# hw2.net
KiCad netlist of a schematic drawn in EAGLE
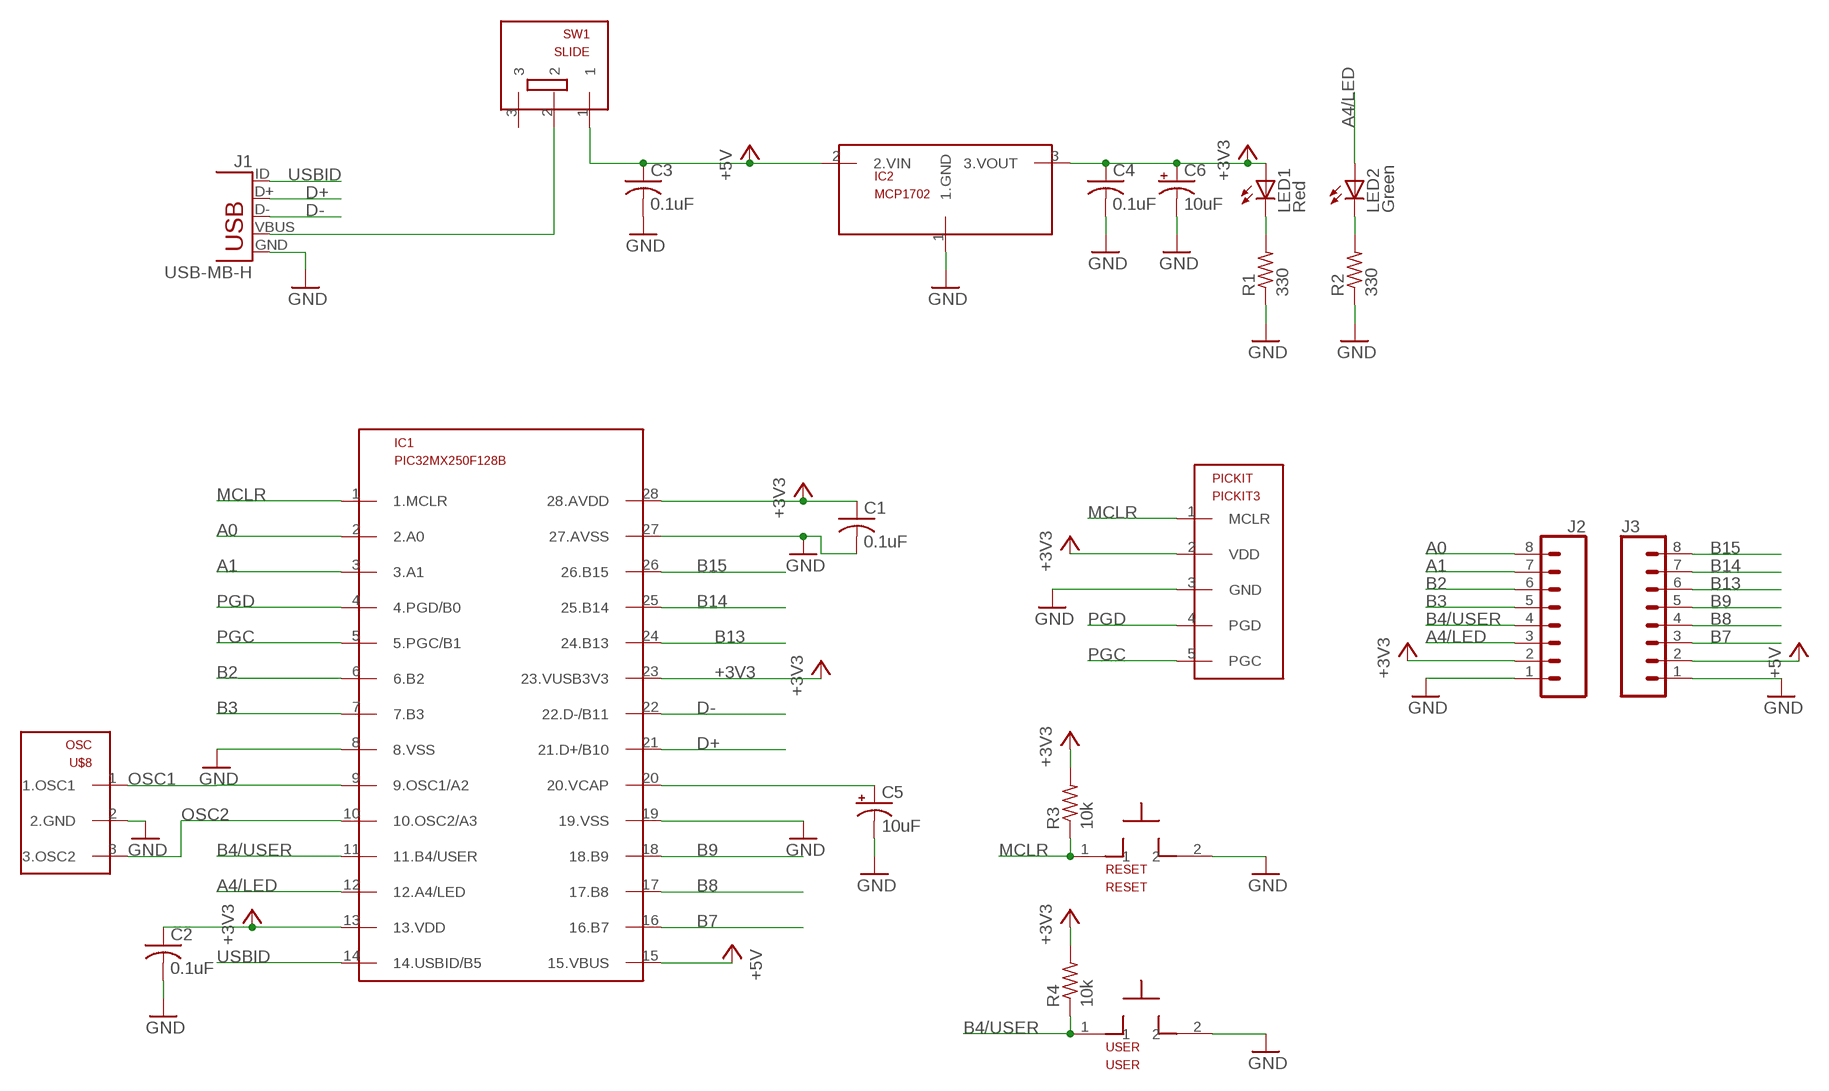
[diagram p0: schematic, sheet 1]

(export (version "E")
  (design (tool "Eeschema 10.0.6"))
  (components
    (comp (ref "C1")
      (value "0.1uF")
      (footprint "eagle-import:C025-025X050")
      (libsource (lib "eagle-import") (part "C-US025-025X050"))
    )
    (comp (ref "C2")
      (value "0.1uF")
      (footprint "eagle-import:C025-025X050")
      (libsource (lib "eagle-import") (part "C-US025-025X050"))
    )
    (comp (ref "C3")
      (value "0.1uF")
      (footprint "eagle-import:C025-025X050")
      (libsource (lib "eagle-import") (part "C-US025-025X050"))
    )
    (comp (ref "C4")
      (value "0.1uF")
      (footprint "eagle-import:C025-025X050")
      (libsource (lib "eagle-import") (part "C-US025-025X050"))
    )
    (comp (ref "C5")
      (value "10uF")
      (footprint "eagle-import:B45181B")
      (libsource (lib "eagle-import") (part "CPOL-USB45181B"))
    )
    (comp (ref "C6")
      (value "10uF")
      (footprint "eagle-import:B45181B")
      (libsource (lib "eagle-import") (part "CPOL-USB45181B"))
    )
    (comp (ref "IC1")
      (value "PIC32MX250F128B")
      (footprint "eagle-import:DIL28-3")
      (libsource (lib "eagle-import") (part "PIC32MX250F128B"))
    )
    (comp (ref "IC2")
      (value "MCP1702")
      (footprint "eagle-import:TO92")
      (libsource (lib "eagle-import") (part "MCP1702"))
    )
    (comp (ref "J1")
      (value "USB-MB-H")
      (footprint "eagle-import:USB-MB-H")
      (libsource (lib "eagle-import") (part "USB-MB-H"))
    )
    (comp (ref "J2")
      (value "CONN_08\"")
      (footprint "eagle-import:1X08")
      (libsource (lib "eagle-import") (part "CONN_08{dblquote}"))
    )
    (comp (ref "J3")
      (value "CONN_08\"")
      (footprint "eagle-import:1X08")
      (libsource (lib "eagle-import") (part "CONN_08{dblquote}"))
    )
    (comp (ref "LED1")
      (value "Red")
      (footprint "eagle-import:LED3MM")
      (libsource (lib "eagle-import") (part "LED3MM"))
    )
    (comp (ref "LED2")
      (value "Green")
      (footprint "eagle-import:LED3MM")
      (libsource (lib "eagle-import") (part "LED3MM"))
    )
    (comp (ref "PICKIT")
      (value "PICKIT3")
      (footprint "eagle-import:1X05")
      (libsource (lib "eagle-import") (part "PICKIT3"))
    )
    (comp (ref "R1")
      (value "330")
      (footprint "eagle-import:0207_10")
      (libsource (lib "eagle-import") (part "R-US_0207/10"))
    )
    (comp (ref "R2")
      (value "330")
      (footprint "eagle-import:0207_10")
      (libsource (lib "eagle-import") (part "R-US_0207/10"))
    )
    (comp (ref "R3")
      (value "10k")
      (footprint "eagle-import:0207_10")
      (libsource (lib "eagle-import") (part "R-US_0207/10"))
    )
    (comp (ref "R4")
      (value "10k")
      (footprint "eagle-import:0207_10")
      (libsource (lib "eagle-import") (part "R-US_0207/10"))
    )
    (comp (ref "RESET")
      (value "RESET")
      (footprint "eagle-import:PB")
      (libsource (lib "eagle-import") (part "PB"))
    )
    (comp (ref "SW1")
      (value "SLIDE")
      (footprint "eagle-import:SLIDE")
      (libsource (lib "eagle-import") (part "SLIDE"))
    )
    (comp (ref "U$8")
      (value "OSC")
      (footprint "eagle-import:OSC")
      (libsource (lib "eagle-import") (part "OSC"))
    )
    (comp (ref "USER")
      (value "USER")
      (footprint "eagle-import:PB")
      (libsource (lib "eagle-import") (part "PB"))
    )
  )
  (nets
    (net (code "1") (name "+3V3") (class "Default")
      (node (ref "C1") (pin "1") (pinfunction "1_1") (pintype "passive"))
      (node (ref "C2") (pin "1") (pinfunction "1_1") (pintype "passive"))
      (node (ref "C4") (pin "1") (pinfunction "1_1") (pintype "passive"))
      (node (ref "C6") (pin "+") (pinfunction "+_+") (pintype "passive"))
      (node (ref "IC1") (pin "13") (pinfunction "13.VDD_13") (pintype "bidirectional"))
      (node (ref "IC1") (pin "23") (pinfunction "23.VUSB3V3_23") (pintype "bidirectional"))
      (node (ref "IC1") (pin "28") (pinfunction "28.AVDD_28") (pintype "bidirectional"))
      (node (ref "IC2") (pin "3") (pinfunction "3.VOUT_3") (pintype "bidirectional"))
      (node (ref "J2") (pin "2") (pinfunction "2_2") (pintype "passive"))
      (node (ref "LED1") (pin "A") (pinfunction "A_A") (pintype "passive"))
      (node (ref "PICKIT") (pin "2") (pinfunction "VDD_2") (pintype "bidirectional"))
      (node (ref "R3") (pin "2") (pinfunction "2_2") (pintype "passive"))
      (node (ref "R4") (pin "2") (pinfunction "2_2") (pintype "passive"))
    )
    (net (code "2") (name "+5V") (class "Default")
      (node (ref "C3") (pin "1") (pinfunction "1_1") (pintype "passive"))
      (node (ref "IC1") (pin "15") (pinfunction "15.VBUS_15") (pintype "bidirectional"))
      (node (ref "IC2") (pin "2") (pinfunction "2.VIN_2") (pintype "bidirectional"))
      (node (ref "J3") (pin "2") (pinfunction "2_2") (pintype "passive"))
      (node (ref "SW1") (pin "1") (pinfunction "1_1") (pintype "bidirectional"))
    )
    (net (code "3") (name "/A0") (class "Default")
      (node (ref "IC1") (pin "2") (pinfunction "2.A0_2") (pintype "bidirectional"))
      (node (ref "J2") (pin "8") (pinfunction "8_8") (pintype "passive"))
    )
    (net (code "4") (name "/A1") (class "Default")
      (node (ref "IC1") (pin "3") (pinfunction "3.A1_3") (pintype "bidirectional"))
      (node (ref "J2") (pin "7") (pinfunction "7_7") (pintype "passive"))
    )
    (net (code "5") (name "/A4{slash}LED") (class "Default")
      (node (ref "IC1") (pin "12") (pinfunction "12.A4/LED_12") (pintype "bidirectional"))
      (node (ref "J2") (pin "3") (pinfunction "3_3") (pintype "passive"))
      (node (ref "LED2") (pin "A") (pinfunction "A_A") (pintype "passive"))
    )
    (net (code "6") (name "/B2") (class "Default")
      (node (ref "IC1") (pin "6") (pinfunction "6.B2_6") (pintype "bidirectional"))
      (node (ref "J2") (pin "6") (pinfunction "6_6") (pintype "passive"))
    )
    (net (code "7") (name "/B3") (class "Default")
      (node (ref "IC1") (pin "7") (pinfunction "7.B3_7") (pintype "bidirectional"))
      (node (ref "J2") (pin "5") (pinfunction "5_5") (pintype "passive"))
    )
    (net (code "8") (name "/B4{slash}USER") (class "Default")
      (node (ref "IC1") (pin "11") (pinfunction "11.B4/USER_11") (pintype "bidirectional"))
      (node (ref "J2") (pin "4") (pinfunction "4_4") (pintype "passive"))
      (node (ref "R4") (pin "1") (pinfunction "1_1") (pintype "passive"))
      (node (ref "USER") (pin "1") (pinfunction "1_1") (pintype "bidirectional"))
    )
    (net (code "9") (name "/B7") (class "Default")
      (node (ref "IC1") (pin "16") (pinfunction "16.B7_16") (pintype "bidirectional"))
      (node (ref "J3") (pin "3") (pinfunction "3_3") (pintype "passive"))
    )
    (net (code "10") (name "/B8") (class "Default")
      (node (ref "IC1") (pin "17") (pinfunction "17.B8_17") (pintype "bidirectional"))
      (node (ref "J3") (pin "4") (pinfunction "4_4") (pintype "passive"))
    )
    (net (code "11") (name "/B9") (class "Default")
      (node (ref "IC1") (pin "18") (pinfunction "18.B9_18") (pintype "bidirectional"))
      (node (ref "J3") (pin "5") (pinfunction "5_5") (pintype "passive"))
    )
    (net (code "12") (name "/B13") (class "Default")
      (node (ref "IC1") (pin "24") (pinfunction "24.B13_24") (pintype "bidirectional"))
      (node (ref "J3") (pin "6") (pinfunction "6_6") (pintype "passive"))
    )
    (net (code "13") (name "/B14") (class "Default")
      (node (ref "IC1") (pin "25") (pinfunction "25.B14_25") (pintype "bidirectional"))
      (node (ref "J3") (pin "7") (pinfunction "7_7") (pintype "passive"))
    )
    (net (code "14") (name "/B15") (class "Default")
      (node (ref "IC1") (pin "26") (pinfunction "26.B15_26") (pintype "bidirectional"))
      (node (ref "J3") (pin "8") (pinfunction "8_8") (pintype "passive"))
    )
    (net (code "15") (name "/D+") (class "Default")
      (node (ref "IC1") (pin "21") (pinfunction "21.D+/B10_21") (pintype "bidirectional"))
      (node (ref "J1") (pin "D+") (pinfunction "D+_D+") (pintype "bidirectional"))
    )
    (net (code "16") (name "/D-") (class "Default")
      (node (ref "IC1") (pin "22") (pinfunction "22.D-/B11_22") (pintype "bidirectional"))
      (node (ref "J1") (pin "D-") (pinfunction "D-_D-") (pintype "bidirectional"))
    )
    (net (code "17") (name "/MCLR") (class "Default")
      (node (ref "IC1") (pin "1") (pinfunction "1.MCLR_1") (pintype "bidirectional"))
      (node (ref "PICKIT") (pin "1") (pinfunction "MCLR_1") (pintype "bidirectional"))
      (node (ref "R3") (pin "1") (pinfunction "1_1") (pintype "passive"))
      (node (ref "RESET") (pin "1") (pinfunction "1_1") (pintype "bidirectional"))
    )
    (net (code "18") (name "/OSC1") (class "Default")
      (node (ref "IC1") (pin "9") (pinfunction "9.OSC1/A2_9") (pintype "bidirectional"))
      (node (ref "U$8") (pin "1") (pinfunction "1.OSC1_1") (pintype "bidirectional"))
    )
    (net (code "19") (name "/OSC2") (class "Default")
      (node (ref "IC1") (pin "10") (pinfunction "10.OSC2/A3_10") (pintype "bidirectional"))
      (node (ref "U$8") (pin "3") (pinfunction "3.OSC2_3") (pintype "bidirectional"))
    )
    (net (code "20") (name "/PGC") (class "Default")
      (node (ref "IC1") (pin "5") (pinfunction "5.PGC/B1_5") (pintype "bidirectional"))
      (node (ref "PICKIT") (pin "5") (pinfunction "PGC_5") (pintype "bidirectional"))
    )
    (net (code "21") (name "/PGD") (class "Default")
      (node (ref "IC1") (pin "4") (pinfunction "4.PGD/B0_4") (pintype "bidirectional"))
      (node (ref "PICKIT") (pin "4") (pinfunction "PGD_4") (pintype "bidirectional"))
    )
    (net (code "22") (name "/USBID") (class "Default")
      (node (ref "IC1") (pin "14") (pinfunction "14.USBID/B5_14") (pintype "bidirectional"))
      (node (ref "J1") (pin "ID") (pinfunction "ID_ID") (pintype "bidirectional"))
    )
    (net (code "23") (name "GND") (class "Default")
      (node (ref "C1") (pin "2") (pinfunction "2_2") (pintype "passive"))
      (node (ref "C2") (pin "2") (pinfunction "2_2") (pintype "passive"))
      (node (ref "C3") (pin "2") (pinfunction "2_2") (pintype "passive"))
      (node (ref "C4") (pin "2") (pinfunction "2_2") (pintype "passive"))
      (node (ref "C5") (pin "-") (pinfunction "-_-") (pintype "passive"))
      (node (ref "C6") (pin "-") (pinfunction "-_-") (pintype "passive"))
      (node (ref "IC1") (pin "19") (pinfunction "19.VSS_19") (pintype "bidirectional"))
      (node (ref "IC1") (pin "27") (pinfunction "27.AVSS_27") (pintype "bidirectional"))
      (node (ref "IC1") (pin "8") (pinfunction "8.VSS_8") (pintype "bidirectional"))
      (node (ref "IC2") (pin "1") (pinfunction "1.GND_1") (pintype "bidirectional"))
      (node (ref "J1") (pin "GND") (pinfunction "GND_GND") (pintype "bidirectional"))
      (node (ref "J2") (pin "1") (pinfunction "1_1") (pintype "passive"))
      (node (ref "J3") (pin "1") (pinfunction "1_1") (pintype "passive"))
      (node (ref "PICKIT") (pin "3") (pinfunction "GND_3") (pintype "bidirectional"))
      (node (ref "R1") (pin "1") (pinfunction "1_1") (pintype "passive"))
      (node (ref "R2") (pin "1") (pinfunction "1_1") (pintype "passive"))
      (node (ref "RESET") (pin "2") (pinfunction "2_2") (pintype "bidirectional"))
      (node (ref "U$8") (pin "2") (pinfunction "2.GND_2") (pintype "bidirectional"))
      (node (ref "USER") (pin "2") (pinfunction "2_2") (pintype "bidirectional"))
    )
    (net (code "24") (name "Net-(IC1-20.VCAP)") (class "Default")
      (node (ref "C5") (pin "+") (pinfunction "+_+") (pintype "passive"))
      (node (ref "IC1") (pin "20") (pinfunction "20.VCAP_20") (pintype "bidirectional"))
    )
    (net (code "25") (name "Net-(J1-PadVBUS)") (class "Default")
      (node (ref "J1") (pin "VBUS") (pinfunction "VBUS_VBUS") (pintype "bidirectional"))
      (node (ref "SW1") (pin "2") (pinfunction "2_2") (pintype "bidirectional"))
    )
    (net (code "26") (name "Net-(LED1-C)") (class "Default")
      (node (ref "LED1") (pin "K") (pinfunction "C_K") (pintype "passive"))
      (node (ref "R1") (pin "2") (pinfunction "2_2") (pintype "passive"))
    )
    (net (code "27") (name "Net-(LED2-C)") (class "Default")
      (node (ref "LED2") (pin "K") (pinfunction "C_K") (pintype "passive"))
      (node (ref "R2") (pin "2") (pinfunction "2_2") (pintype "passive"))
    )
    (net (code "28") (name "unconnected-(SW1-Pad3)") (class "Default")
      (node (ref "SW1") (pin "3") (pinfunction "3_3") (pintype "bidirectional"))
    )
  )
)
